# DAC_32CH.net
KiCad netlist of a schematic drawn in Altium Designer
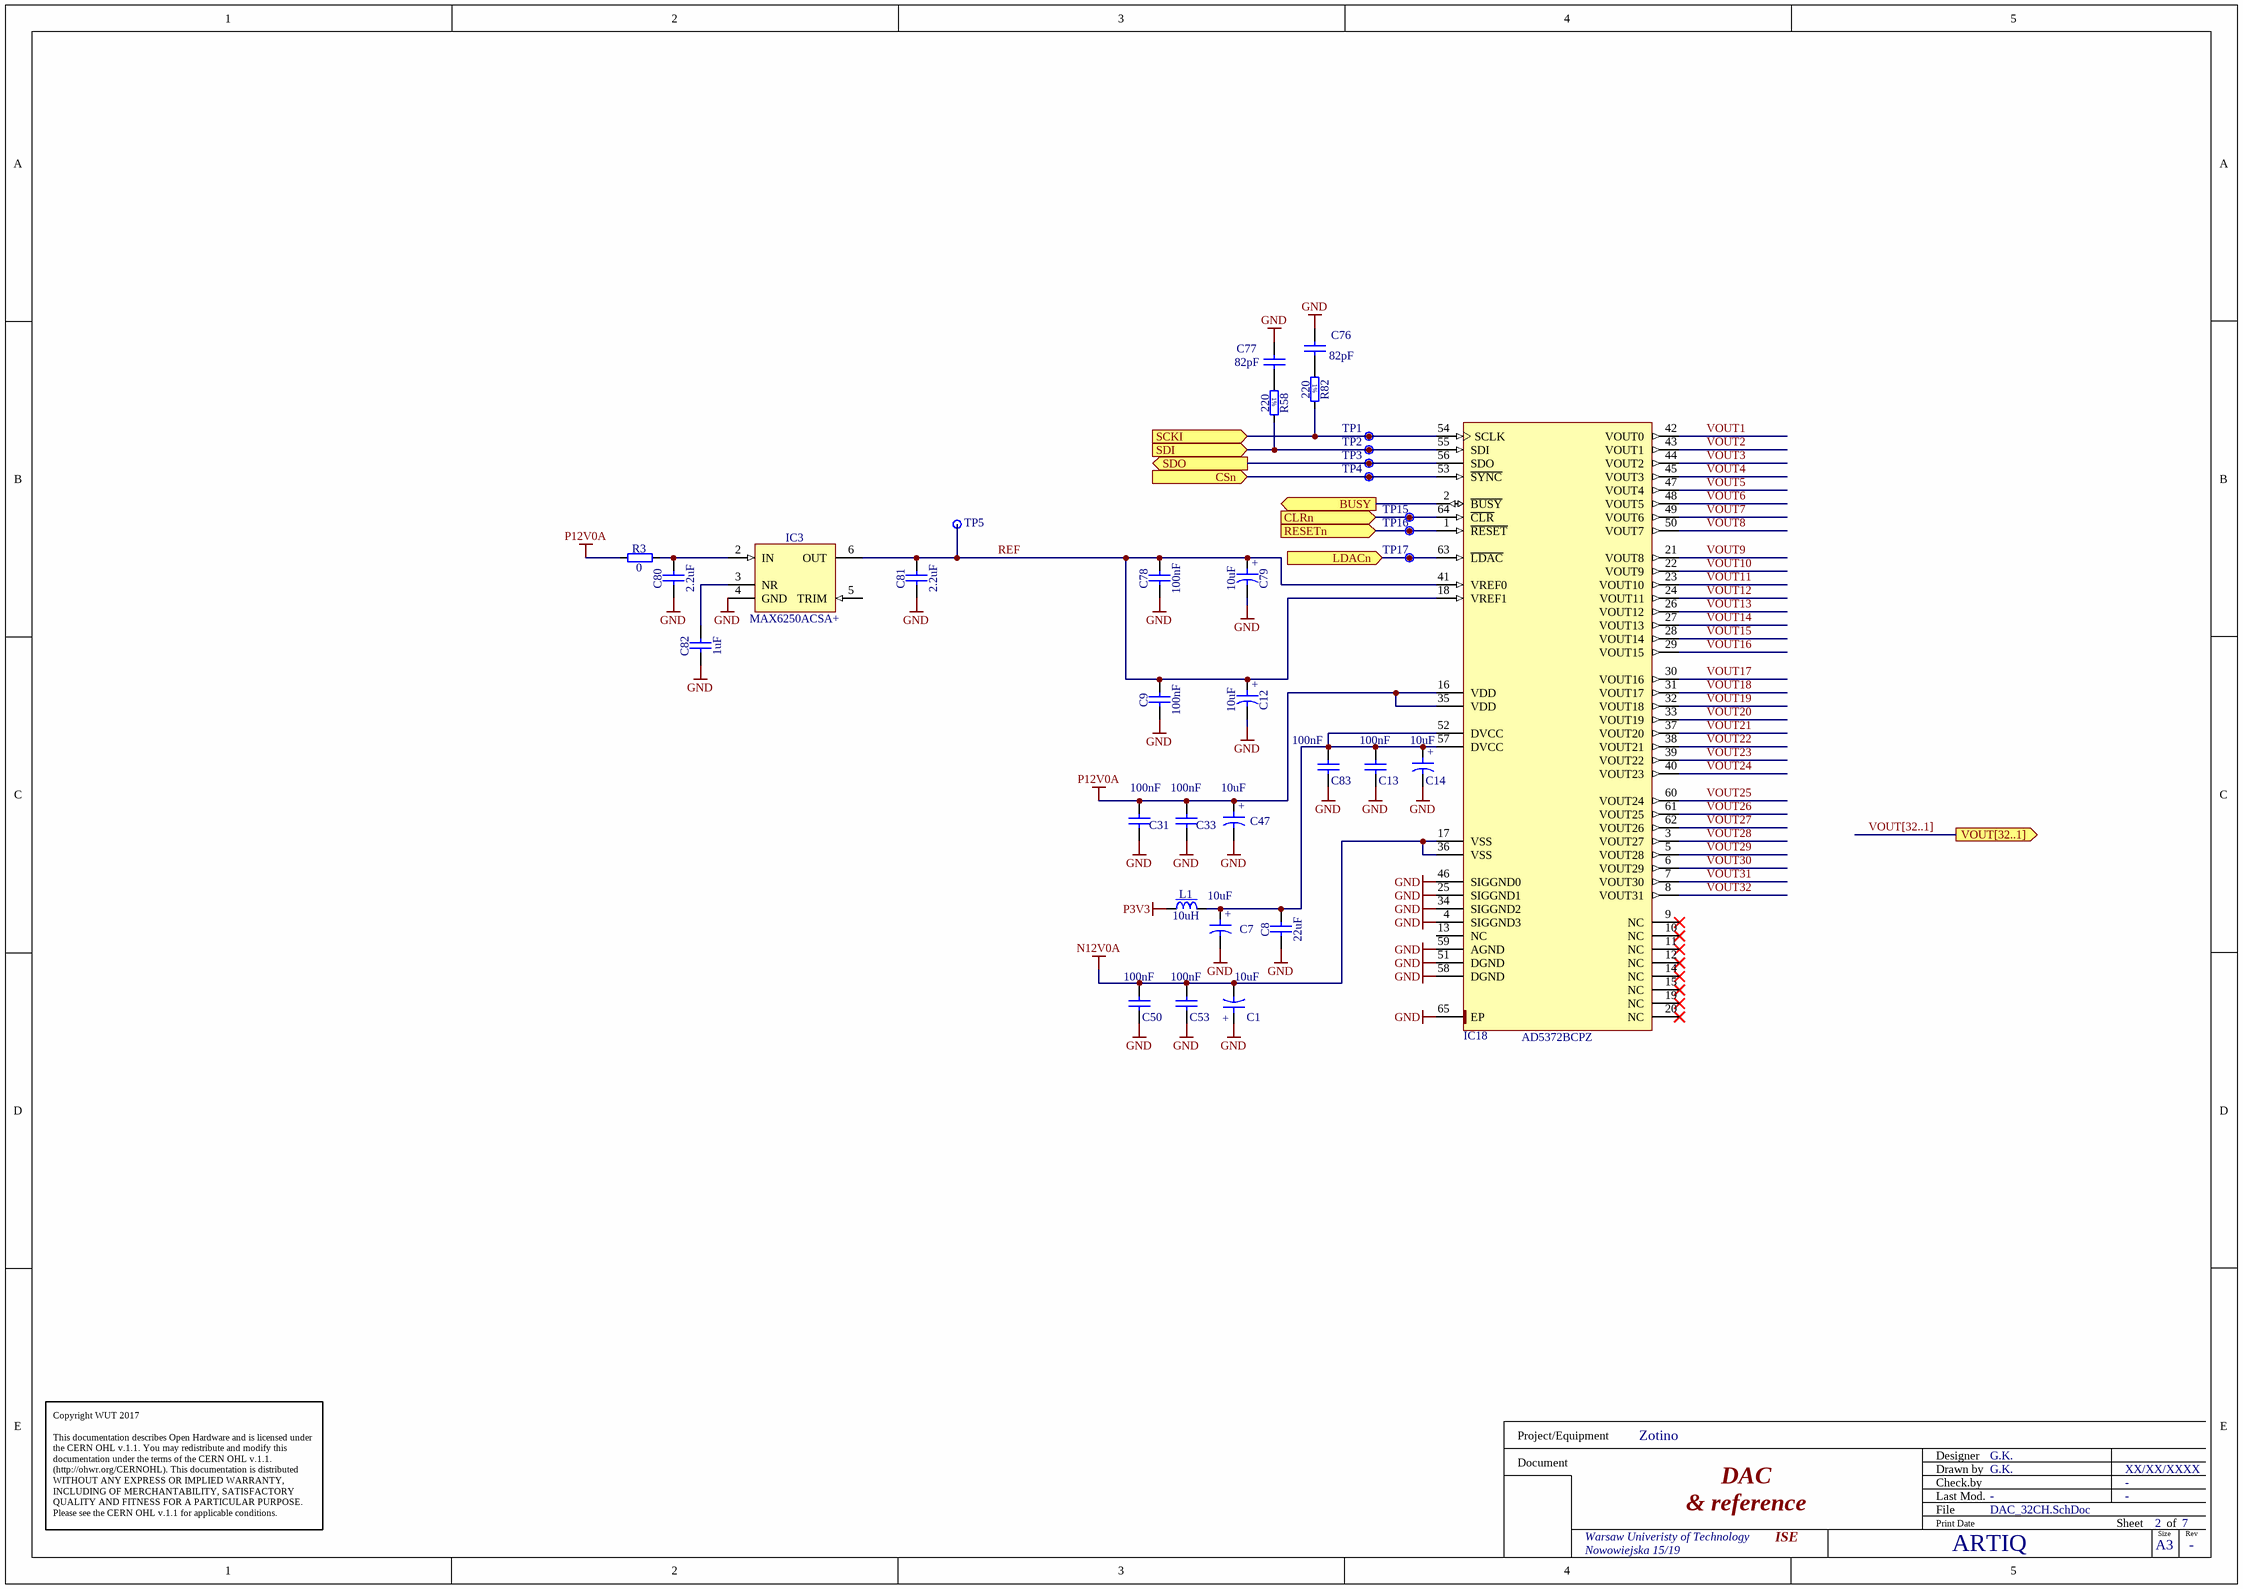
[diagram p0: DAC_32CH.SchDoc]

(export (version "E")
  (design (tool "Eeschema 10.0.6"))
  (components
    (comp (ref "C1")
      (value "10uF")
      (footprint "CAPMP3216X180N")
      (description "Polarised capacitor")
      (fields
        (field (name "PART NUMBER") "CTE3216-18_10UF_16V_20%_AVX_TCJ")
        (field (name "VOLTAGE") "16V")
        (field (name "AUTHOR") "CERN DEM JLC")
      )
      (libsource (lib "Capacitors") (part "Capacitor - polarized"))
    )
    (comp (ref "C7")
      (value "10uF")
      (footprint "CAPMP3216X180N")
      (description "Polarised capacitor")
      (fields
        (field (name "PART NUMBER") "CTE3216-18_10UF_16V_20%_AVX_TCJ")
        (field (name "VOLTAGE") "16V")
        (field (name "AUTHOR") "CERN DEM JLC")
      )
      (libsource (lib "Capacitors") (part "Capacitor - polarized"))
    )
    (comp (ref "C8")
      (value "22uF")
      (footprint "CAPC2012X135N")
      (description "Non-polarised capacitor")
      (fields
        (field (name "PART NUMBER") "CC0805_22UF_16V_10%_X5R")
        (field (name "VOLTAGE") "16V")
        (field (name "AUTHOR") "CERN DEM JLC")
      )
      (libsource (lib "Capacitors") (part "Capacitor - non polarized"))
    )
    (comp (ref "C9")
      (value "100nF")
      (footprint "CAPC1005X55N")
      (description "Non-polarised capacitor")
      (fields
        (field (name "PART NUMBER") "CC0402_100NF_16V_10%_X7R")
        (field (name "VOLTAGE") "16V")
        (field (name "AUTHOR") "CERN DEM JLC")
      )
      (libsource (lib "Capacitors") (part "Capacitor - non polarized"))
    )
    (comp (ref "C12")
      (value "10uF")
      (footprint "CAPMP3216X180N")
      (description "Polarised capacitor")
      (fields
        (field (name "PART NUMBER") "CTE3216-18_10UF_16V_20%_AVX_TCJ")
        (field (name "VOLTAGE") "16V")
        (field (name "AUTHOR") "CERN DEM JLC")
      )
      (libsource (lib "Capacitors") (part "Capacitor - polarized"))
    )
    (comp (ref "C13")
      (value "100nF")
      (footprint "CAPC1005X55N")
      (description "Non-polarised capacitor")
      (fields
        (field (name "PART NUMBER") "CC0402_100NF_16V_10%_X7R")
        (field (name "VOLTAGE") "16V")
        (field (name "AUTHOR") "CERN DEM JLC")
      )
      (libsource (lib "Capacitors") (part "Capacitor - non polarized"))
    )
    (comp (ref "C14")
      (value "10uF")
      (footprint "CAPMP3216X180N")
      (description "Polarised capacitor")
      (fields
        (field (name "PART NUMBER") "CTE3216-18_10UF_16V_20%_AVX_TCJ")
        (field (name "VOLTAGE") "16V")
        (field (name "AUTHOR") "CERN DEM JLC")
      )
      (libsource (lib "Capacitors") (part "Capacitor - polarized"))
    )
    (comp (ref "C31")
      (value "100nF")
      (footprint "CAPC1005X55N")
      (description "Non-polarised capacitor")
      (fields
        (field (name "PART NUMBER") "CC0402_100NF_16V_10%_X7R")
        (field (name "VOLTAGE") "16V")
        (field (name "AUTHOR") "CERN DEM JLC")
      )
      (libsource (lib "Capacitors") (part "Capacitor - non polarized"))
    )
    (comp (ref "C33")
      (value "100nF")
      (footprint "CAPC1005X55N")
      (description "Non-polarised capacitor")
      (fields
        (field (name "PART NUMBER") "CC0402_100NF_16V_10%_X7R")
        (field (name "VOLTAGE") "16V")
        (field (name "AUTHOR") "CERN DEM JLC")
      )
      (libsource (lib "Capacitors") (part "Capacitor - non polarized"))
    )
    (comp (ref "C47")
      (value "10uF")
      (footprint "CAPMP3216X180N")
      (description "Polarised capacitor")
      (fields
        (field (name "PART NUMBER") "CTE3216-18_10UF_16V_20%_AVX_TCJ")
        (field (name "VOLTAGE") "16V")
        (field (name "AUTHOR") "CERN DEM JLC")
      )
      (libsource (lib "Capacitors") (part "Capacitor - polarized"))
    )
    (comp (ref "C50")
      (value "100nF")
      (footprint "CAPC1005X55N")
      (description "Non-polarised capacitor")
      (fields
        (field (name "PART NUMBER") "CC0402_100NF_16V_10%_X7R")
        (field (name "VOLTAGE") "16V")
        (field (name "AUTHOR") "CERN DEM JLC")
      )
      (libsource (lib "Capacitors") (part "Capacitor - non polarized"))
    )
    (comp (ref "C53")
      (value "100nF")
      (footprint "CAPC1005X55N")
      (description "Non-polarised capacitor")
      (fields
        (field (name "PART NUMBER") "CC0402_100NF_16V_10%_X7R")
        (field (name "VOLTAGE") "16V")
        (field (name "AUTHOR") "CERN DEM JLC")
      )
      (libsource (lib "Capacitors") (part "Capacitor - non polarized"))
    )
    (comp (ref "C76")
      (value "82pF")
      (footprint "CAPC1608X87N")
      (description "Non-polarised capacitor")
      (fields
        (field (name "PART NUMBER") "CC0603_82PF_50V_5%_NP0")
        (field (name "VOLTAGE") "50V")
        (field (name "AUTHOR") "CERN DEM JLC")
      )
      (libsource (lib "Capacitors") (part "Capacitor - non polarized"))
    )
    (comp (ref "C77")
      (value "82pF")
      (footprint "CAPC1608X87N")
      (description "Non-polarised capacitor")
      (fields
        (field (name "PART NUMBER") "CC0603_82PF_50V_5%_NP0")
        (field (name "VOLTAGE") "50V")
        (field (name "AUTHOR") "CERN DEM JLC")
      )
      (libsource (lib "Capacitors") (part "Capacitor - non polarized"))
    )
    (comp (ref "C78")
      (value "100nF")
      (footprint "CAPC1005X55N")
      (description "Non-polarised capacitor")
      (fields
        (field (name "PART NUMBER") "CC0402_100NF_16V_10%_X7R")
        (field (name "VOLTAGE") "16V")
        (field (name "AUTHOR") "CERN DEM JLC")
      )
      (libsource (lib "Capacitors") (part "Capacitor - non polarized"))
    )
    (comp (ref "C79")
      (value "10uF")
      (footprint "CAPMP3216X180N")
      (description "Polarised capacitor")
      (fields
        (field (name "PART NUMBER") "CTE3216-18_10UF_16V_20%_AVX_TCJ")
        (field (name "VOLTAGE") "16V")
        (field (name "AUTHOR") "CERN DEM JLC")
      )
      (libsource (lib "Capacitors") (part "Capacitor - polarized"))
    )
    (comp (ref "C80")
      (value "2.2uF")
      (footprint "CAPC1608X87N")
      (description "Non-polarised capacitor")
      (fields
        (field (name "PART NUMBER") "CC0603_2.2UF_16V_10%_X5R")
        (field (name "VOLTAGE") "16V")
        (field (name "AUTHOR") "CERN DEM JLC")
      )
      (libsource (lib "Capacitors") (part "Capacitor - non polarized"))
    )
    (comp (ref "C81")
      (value "2.2uF")
      (footprint "CAPC1608X87N")
      (description "Non-polarised capacitor")
      (fields
        (field (name "PART NUMBER") "CC0603_2.2UF_16V_10%_X5R")
        (field (name "VOLTAGE") "16V")
        (field (name "AUTHOR") "CERN DEM JLC")
      )
      (libsource (lib "Capacitors") (part "Capacitor - non polarized"))
    )
    (comp (ref "C82")
      (value "1uF")
      (footprint "CAPC1608X87N")
      (description "Non-polarised capacitor")
      (fields
        (field (name "PART NUMBER") "CC0603_1UF_25V_10%_X7R")
        (field (name "VOLTAGE") "25V")
        (field (name "AUTHOR") "CERN DEM JLC")
      )
      (libsource (lib "Capacitors") (part "Capacitor - non polarized"))
    )
    (comp (ref "C83")
      (value "100nF")
      (footprint "CAPC1005X55N")
      (description "Non-polarised capacitor")
      (fields
        (field (name "PART NUMBER") "CC0402_100NF_16V_10%_X7R")
        (field (name "VOLTAGE") "16V")
        (field (name "AUTHOR") "CERN DEM JLC")
      )
      (libsource (lib "Capacitors") (part "Capacitor - non polarized"))
    )
    (comp (ref "IC3")
      (value "MAX6250ACSA+")
      (footprint "SOIC127P600X175-8N")
      (description "1ppm/°C, Low-Noise, Precision, +5.000V Voltage Reference")
      (fields (field (name "MANUFACTURER") "MAXIM") (field (name "AUTHOR") "CERN DEM JMW"))
      (libsource (lib "ICs And Semiconductors") (part "MAX6250"))
    )
    (comp (ref "IC18")
      (value "AD5372BCPZ")
      (footprint "QFN50P900X900X100-65N-S725")
      (description "32-Channel, 16-Bit, Serial Input, Voltage Output Digital-to-Analog Converter")
      (fields (field (name "MANUFACTURER") "ANALOG DEVICES") (field (name "AUTHOR") "GK"))
      (libsource (lib "LIBRARY_SCH") (part "DAC_AD5372"))
    )
    (comp (ref "L1")
      (value "10uH")
      (footprint "IND_MURATA-PS_8400")
      (description "Inductor With Core")
      (fields
        (field (name "PART NUMBER") "IND_10UH_10%_MURATA-PS_8400")
        (field (name "POWER") "950mA")
        (field (name "AUTHOR") "CERN DEM JLC")
      )
      (libsource (lib "Inductors & Transformers") (part "Inductor With Magnetic core"))
    )
    (comp (ref "R3")
      (value "0")
      (footprint "RESC1005X40N")
      (description "Resistor")
      (fields
        (field (name "PART NUMBER") "R0402_0R_JUMPER")
        (field (name "MANUFACTURER") "GENERIC")
        (field (name "AUTHOR") "CERN DEM JLC")
      )
      (libsource (lib "Resistors") (part "Resistor"))
    )
    (comp (ref "R58")
      (value "220")
      (footprint "RESC1608X55N")
      (description "Resistor - 1%")
      (fields
        (field (name "PART NUMBER") "R0603_220R_1%_0.1W_100PPM")
        (field (name "POWER") "0.1W")
        (field (name "AUTHOR") "CERN DEM JLC")
      )
      (libsource (lib "Resistors") (part "Resistor - 1%"))
    )
    (comp (ref "R82")
      (value "220")
      (footprint "RESC1608X55N")
      (description "Resistor - 1%")
      (fields
        (field (name "PART NUMBER") "R0603_220R_1%_0.1W_100PPM")
        (field (name "POWER") "0.1W")
        (field (name "AUTHOR") "CERN DEM JLC")
      )
      (libsource (lib "Resistors") (part "Resistor - 1%"))
    )
    (comp (ref "TP1")
      (value "Test Point")
      (footprint "TPS127")
      (fields (field (name "PART NUMBER") "SMD_PAD_1.27X1.27MM") (field (name "AUTHOR") "CERN DEM JLC"))
      (libsource (lib "Eletro-mechanical") (part "Test Point"))
    )
    (comp (ref "TP2")
      (value "Test Point")
      (footprint "TPS127")
      (fields (field (name "PART NUMBER") "SMD_PAD_1.27X1.27MM") (field (name "AUTHOR") "CERN DEM JLC"))
      (libsource (lib "Eletro-mechanical") (part "Test Point"))
    )
    (comp (ref "TP3")
      (value "Test Point")
      (footprint "TPS127")
      (fields (field (name "PART NUMBER") "SMD_PAD_1.27X1.27MM") (field (name "AUTHOR") "CERN DEM JLC"))
      (libsource (lib "Eletro-mechanical") (part "Test Point"))
    )
    (comp (ref "TP4")
      (value "Test Point")
      (footprint "TPS127")
      (fields (field (name "PART NUMBER") "SMD_PAD_1.27X1.27MM") (field (name "AUTHOR") "CERN DEM JLC"))
      (libsource (lib "Eletro-mechanical") (part "Test Point"))
    )
    (comp (ref "TP5")
      (value "Test Point")
      (footprint "TPS127")
      (fields (field (name "PART NUMBER") "SMD_PAD_1.27X1.27MM") (field (name "AUTHOR") "CERN DEM JLC"))
      (libsource (lib "Eletro-mechanical") (part "Test Point"))
    )
    (comp (ref "TP15")
      (value "Test Point")
      (footprint "TPS127")
      (fields (field (name "PART NUMBER") "SMD_PAD_1.27X1.27MM") (field (name "AUTHOR") "CERN DEM JLC"))
      (libsource (lib "Eletro-mechanical") (part "Test Point"))
    )
    (comp (ref "TP16")
      (value "Test Point")
      (footprint "TPS127")
      (fields (field (name "PART NUMBER") "SMD_PAD_1.27X1.27MM") (field (name "AUTHOR") "CERN DEM JLC"))
      (libsource (lib "Eletro-mechanical") (part "Test Point"))
    )
    (comp (ref "TP17")
      (value "Test Point")
      (footprint "TPS127")
      (fields (field (name "PART NUMBER") "SMD_PAD_1.27X1.27MM") (field (name "AUTHOR") "CERN DEM JLC"))
      (libsource (lib "Eletro-mechanical") (part "Test Point"))
    )
  )
  (nets
    (net (code "1") (name "/BUSY") (class "Default")
      (node (ref "IC18") (pin "2") (pinfunction "~{BUSY}_2") (pintype "bidirectional"))
    )
    (net (code "2") (name "/CLRn") (class "Default")
      (node (ref "IC18") (pin "64") (pinfunction "~{CLR}_64") (pintype "input"))
      (node (ref "TP15") (pin "1") (pinfunction "1_1") (pintype "bidirectional"))
    )
    (net (code "3") (name "/CSn") (class "Default")
      (node (ref "IC18") (pin "53") (pinfunction "~{SYNC}_53") (pintype "input"))
      (node (ref "TP4") (pin "1") (pinfunction "1_1") (pintype "bidirectional"))
    )
    (net (code "4") (name "/LDACn") (class "Default")
      (node (ref "IC18") (pin "63") (pinfunction "~{LDAC}_63") (pintype "input"))
      (node (ref "TP17") (pin "1") (pinfunction "1_1") (pintype "bidirectional"))
    )
    (net (code "5") (name "/REF") (class "Default")
      (node (ref "C12") (pin "1") (pinfunction "1_1") (pintype "passive"))
      (node (ref "C78") (pin "2") (pinfunction "2_2") (pintype "passive"))
      (node (ref "C79") (pin "1") (pinfunction "1_1") (pintype "passive"))
      (node (ref "C81") (pin "2") (pinfunction "2_2") (pintype "passive"))
      (node (ref "C9") (pin "2") (pinfunction "2_2") (pintype "passive"))
      (node (ref "IC18") (pin "18") (pinfunction "VREF1_18") (pintype "input"))
      (node (ref "IC18") (pin "41") (pinfunction "VREF0_41") (pintype "input"))
      (node (ref "IC3") (pin "6") (pinfunction "OUT_6") (pintype "power_in"))
      (node (ref "TP5") (pin "1") (pinfunction "1_1") (pintype "bidirectional"))
    )
    (net (code "6") (name "/RESETn") (class "Default")
      (node (ref "IC18") (pin "1") (pinfunction "~{RESET}_1") (pintype "input"))
      (node (ref "TP16") (pin "1") (pinfunction "1_1") (pintype "bidirectional"))
    )
    (net (code "7") (name "/SCKI") (class "Default")
      (node (ref "IC18") (pin "54") (pinfunction "SCLK_54") (pintype "input"))
      (node (ref "R82") (pin "2") (pinfunction "2_2") (pintype "passive"))
      (node (ref "TP1") (pin "1") (pinfunction "1_1") (pintype "bidirectional"))
    )
    (net (code "8") (name "/SDI") (class "Default")
      (node (ref "IC18") (pin "55") (pinfunction "SDI_55") (pintype "input"))
      (node (ref "R58") (pin "2") (pinfunction "2_2") (pintype "passive"))
      (node (ref "TP2") (pin "1") (pinfunction "1_1") (pintype "bidirectional"))
    )
    (net (code "9") (name "/SDO") (class "Default")
      (node (ref "IC18") (pin "56") (pinfunction "SDO_56") (pintype "tri_state"))
      (node (ref "TP3") (pin "1") (pinfunction "1_1") (pintype "bidirectional"))
    )
    (net (code "10") (name "/VOUT1") (class "Default")
      (node (ref "IC18") (pin "42") (pinfunction "VOUT0_42") (pintype "output"))
    )
    (net (code "11") (name "/VOUT2") (class "Default")
      (node (ref "IC18") (pin "43") (pinfunction "VOUT1_43") (pintype "output"))
    )
    (net (code "12") (name "/VOUT3") (class "Default")
      (node (ref "IC18") (pin "44") (pinfunction "VOUT2_44") (pintype "output"))
    )
    (net (code "13") (name "/VOUT4") (class "Default")
      (node (ref "IC18") (pin "45") (pinfunction "VOUT3_45") (pintype "output"))
    )
    (net (code "14") (name "/VOUT5") (class "Default")
      (node (ref "IC18") (pin "47") (pinfunction "VOUT4_47") (pintype "output"))
    )
    (net (code "15") (name "/VOUT6") (class "Default")
      (node (ref "IC18") (pin "48") (pinfunction "VOUT5_48") (pintype "output"))
    )
    (net (code "16") (name "/VOUT7") (class "Default")
      (node (ref "IC18") (pin "49") (pinfunction "VOUT6_49") (pintype "output"))
    )
    (net (code "17") (name "/VOUT8") (class "Default")
      (node (ref "IC18") (pin "50") (pinfunction "VOUT7_50") (pintype "output"))
    )
    (net (code "18") (name "/VOUT9") (class "Default")
      (node (ref "IC18") (pin "21") (pinfunction "VOUT8_21") (pintype "output"))
    )
    (net (code "19") (name "/VOUT10") (class "Default")
      (node (ref "IC18") (pin "22") (pinfunction "VOUT9_22") (pintype "output"))
    )
    (net (code "20") (name "/VOUT11") (class "Default")
      (node (ref "IC18") (pin "23") (pinfunction "VOUT10_23") (pintype "output"))
    )
    (net (code "21") (name "/VOUT12") (class "Default")
      (node (ref "IC18") (pin "24") (pinfunction "VOUT11_24") (pintype "output"))
    )
    (net (code "22") (name "/VOUT13") (class "Default")
      (node (ref "IC18") (pin "26") (pinfunction "VOUT12_26") (pintype "output"))
    )
    (net (code "23") (name "/VOUT14") (class "Default")
      (node (ref "IC18") (pin "27") (pinfunction "VOUT13_27") (pintype "output"))
    )
    (net (code "24") (name "/VOUT15") (class "Default")
      (node (ref "IC18") (pin "28") (pinfunction "VOUT14_28") (pintype "output"))
    )
    (net (code "25") (name "/VOUT16") (class "Default")
      (node (ref "IC18") (pin "29") (pinfunction "VOUT15_29") (pintype "output"))
    )
    (net (code "26") (name "/VOUT17") (class "Default")
      (node (ref "IC18") (pin "30") (pinfunction "VOUT16_30") (pintype "output"))
    )
    (net (code "27") (name "/VOUT18") (class "Default")
      (node (ref "IC18") (pin "31") (pinfunction "VOUT17_31") (pintype "output"))
    )
    (net (code "28") (name "/VOUT19") (class "Default")
      (node (ref "IC18") (pin "32") (pinfunction "VOUT18_32") (pintype "output"))
    )
    (net (code "29") (name "/VOUT20") (class "Default")
      (node (ref "IC18") (pin "33") (pinfunction "VOUT19_33") (pintype "output"))
    )
    (net (code "30") (name "/VOUT21") (class "Default")
      (node (ref "IC18") (pin "37") (pinfunction "VOUT20_37") (pintype "output"))
    )
    (net (code "31") (name "/VOUT22") (class "Default")
      (node (ref "IC18") (pin "38") (pinfunction "VOUT21_38") (pintype "output"))
    )
    (net (code "32") (name "/VOUT23") (class "Default")
      (node (ref "IC18") (pin "39") (pinfunction "VOUT22_39") (pintype "output"))
    )
    (net (code "33") (name "/VOUT24") (class "Default")
      (node (ref "IC18") (pin "40") (pinfunction "VOUT23_40") (pintype "output"))
    )
    (net (code "34") (name "/VOUT25") (class "Default")
      (node (ref "IC18") (pin "60") (pinfunction "VOUT24_60") (pintype "output"))
    )
    (net (code "35") (name "/VOUT26") (class "Default")
      (node (ref "IC18") (pin "61") (pinfunction "VOUT25_61") (pintype "output"))
    )
    (net (code "36") (name "/VOUT27") (class "Default")
      (node (ref "IC18") (pin "62") (pinfunction "VOUT26_62") (pintype "output"))
    )
    (net (code "37") (name "/VOUT28") (class "Default")
      (node (ref "IC18") (pin "3") (pinfunction "VOUT27_3") (pintype "output"))
    )
    (net (code "38") (name "/VOUT29") (class "Default")
      (node (ref "IC18") (pin "5") (pinfunction "VOUT28_5") (pintype "output"))
    )
    (net (code "39") (name "/VOUT30") (class "Default")
      (node (ref "IC18") (pin "6") (pinfunction "VOUT29_6") (pintype "output"))
    )
    (net (code "40") (name "/VOUT31") (class "Default")
      (node (ref "IC18") (pin "7") (pinfunction "VOUT30_7") (pintype "output"))
    )
    (net (code "41") (name "/VOUT32") (class "Default")
      (node (ref "IC18") (pin "8") (pinfunction "VOUT31_8") (pintype "output"))
    )
    (net (code "43") (name "GND") (class "Default")
      (node (ref "C1") (pin "1") (pinfunction "1_1") (pintype "passive"))
      (node (ref "C12") (pin "2") (pinfunction "2_2") (pintype "passive"))
      (node (ref "C13") (pin "1") (pinfunction "1_1") (pintype "passive"))
      (node (ref "C14") (pin "2") (pinfunction "2_2") (pintype "passive"))
      (node (ref "C31") (pin "1") (pinfunction "1_1") (pintype "passive"))
      (node (ref "C33") (pin "1") (pinfunction "1_1") (pintype "passive"))
      (node (ref "C47") (pin "2") (pinfunction "2_2") (pintype "passive"))
      (node (ref "C50") (pin "1") (pinfunction "1_1") (pintype "passive"))
      (node (ref "C53") (pin "1") (pinfunction "1_1") (pintype "passive"))
      (node (ref "C7") (pin "2") (pinfunction "2_2") (pintype "passive"))
      (node (ref "C76") (pin "1") (pinfunction "1_1") (pintype "passive"))
      (node (ref "C77") (pin "1") (pinfunction "1_1") (pintype "passive"))
      (node (ref "C78") (pin "1") (pinfunction "1_1") (pintype "passive"))
      (node (ref "C79") (pin "2") (pinfunction "2_2") (pintype "passive"))
      (node (ref "C8") (pin "1") (pinfunction "1_1") (pintype "passive"))
      (node (ref "C80") (pin "1") (pinfunction "1_1") (pintype "passive"))
      (node (ref "C81") (pin "1") (pinfunction "1_1") (pintype "passive"))
      (node (ref "C82") (pin "1") (pinfunction "1_1") (pintype "passive"))
      (node (ref "C83") (pin "1") (pinfunction "1_1") (pintype "passive"))
      (node (ref "C9") (pin "1") (pinfunction "1_1") (pintype "passive"))
      (node (ref "IC18") (pin "25") (pinfunction "SIGGND1_25") (pintype "power_in"))
      (node (ref "IC18") (pin "34") (pinfunction "SIGGND2_34") (pintype "power_in"))
      (node (ref "IC18") (pin "4") (pinfunction "SIGGND3_4") (pintype "power_in"))
      (node (ref "IC18") (pin "46") (pinfunction "SIGGND0_46") (pintype "power_in"))
      (node (ref "IC18") (pin "51") (pinfunction "DGND_51") (pintype "power_in"))
      (node (ref "IC18") (pin "58") (pinfunction "DGND_58") (pintype "power_in"))
      (node (ref "IC18") (pin "59") (pinfunction "AGND_59") (pintype "power_in"))
      (node (ref "IC18") (pin "65") (pinfunction "EP_65") (pintype "power_in"))
      (node (ref "IC3") (pin "4") (pinfunction "GND_4") (pintype "power_in"))
    )
    (net (code "44") (name "N12V0A") (class "Default")
      (node (ref "C1") (pin "2") (pinfunction "2_2") (pintype "passive"))
      (node (ref "C50") (pin "2") (pinfunction "2_2") (pintype "passive"))
      (node (ref "C53") (pin "2") (pinfunction "2_2") (pintype "passive"))
      (node (ref "IC18") (pin "17") (pinfunction "VSS_17") (pintype "power_in"))
      (node (ref "IC18") (pin "36") (pinfunction "VSS_36") (pintype "power_in"))
    )
    (net (code "45") (name "Net-(C13-Pad2)") (class "Default")
      (node (ref "C13") (pin "2") (pinfunction "2_2") (pintype "passive"))
      (node (ref "C14") (pin "1") (pinfunction "1_1") (pintype "passive"))
      (node (ref "C7") (pin "1") (pinfunction "1_1") (pintype "passive"))
      (node (ref "C8") (pin "2") (pinfunction "2_2") (pintype "passive"))
      (node (ref "C83") (pin "2") (pinfunction "2_2") (pintype "passive"))
      (node (ref "IC18") (pin "52") (pinfunction "DVCC_52") (pintype "power_in"))
      (node (ref "IC18") (pin "57") (pinfunction "DVCC_57") (pintype "power_in"))
      (node (ref "L1") (pin "2") (pinfunction "2_2") (pintype "passive"))
    )
    (net (code "46") (name "Net-(C76-Pad2)") (class "Default")
      (node (ref "C76") (pin "2") (pinfunction "2_2") (pintype "passive"))
      (node (ref "R82") (pin "1") (pinfunction "1_1") (pintype "passive"))
    )
    (net (code "47") (name "Net-(C77-Pad2)") (class "Default")
      (node (ref "C77") (pin "2") (pinfunction "2_2") (pintype "passive"))
      (node (ref "R58") (pin "1") (pinfunction "1_1") (pintype "passive"))
    )
    (net (code "48") (name "Net-(IC3-IN)") (class "Default")
      (node (ref "C80") (pin "2") (pinfunction "2_2") (pintype "passive"))
      (node (ref "IC3") (pin "2") (pinfunction "IN_2") (pintype "input"))
      (node (ref "R3") (pin "2") (pinfunction "2_2") (pintype "passive"))
    )
    (net (code "49") (name "Net-(IC3-NR)") (class "Default")
      (node (ref "C82") (pin "2") (pinfunction "2_2") (pintype "passive"))
      (node (ref "IC3") (pin "3") (pinfunction "NR_3") (pintype "passive"))
    )
    (net (code "50") (name "P3V3") (class "Default")
      (node (ref "L1") (pin "1") (pinfunction "1_1") (pintype "passive"))
    )
    (net (code "51") (name "P12V0A") (class "Default")
      (node (ref "C31") (pin "2") (pinfunction "2_2") (pintype "passive"))
      (node (ref "C33") (pin "2") (pinfunction "2_2") (pintype "passive"))
      (node (ref "C47") (pin "1") (pinfunction "1_1") (pintype "passive"))
      (node (ref "IC18") (pin "16") (pinfunction "VDD_16") (pintype "power_in"))
      (node (ref "IC18") (pin "35") (pinfunction "VDD_35") (pintype "power_in"))
      (node (ref "R3") (pin "1") (pinfunction "1_1") (pintype "passive"))
    )
    (net (code "52") (name "unconnected-(IC3-TRIM-Pad5)") (class "Default")
      (node (ref "IC3") (pin "5") (pinfunction "TRIM_5") (pintype "input"))
    )
    (net (code "53") (name "unconnected-(IC18-NC-Pad9)") (class "Default")
      (node (ref "IC18") (pin "9") (pinfunction "NC_9") (pintype "passive+no_connect"))
    )
    (net (code "54") (name "unconnected-(IC18-NC-Pad10)") (class "Default")
      (node (ref "IC18") (pin "10") (pinfunction "NC_10") (pintype "passive+no_connect"))
    )
    (net (code "55") (name "unconnected-(IC18-NC-Pad11)") (class "Default")
      (node (ref "IC18") (pin "11") (pinfunction "NC_11") (pintype "passive+no_connect"))
    )
    (net (code "56") (name "unconnected-(IC18-NC-Pad12)") (class "Default")
      (node (ref "IC18") (pin "12") (pinfunction "NC_12") (pintype "passive+no_connect"))
    )
    (net (code "57") (name "unconnected-(IC18-NC-Pad13)") (class "Default")
      (node (ref "IC18") (pin "13") (pinfunction "NC_13") (pintype "passive"))
    )
    (net (code "58") (name "unconnected-(IC18-NC-Pad14)") (class "Default")
      (node (ref "IC18") (pin "14") (pinfunction "NC_14") (pintype "passive+no_connect"))
    )
    (net (code "59") (name "unconnected-(IC18-NC-Pad15)") (class "Default")
      (node (ref "IC18") (pin "15") (pinfunction "NC_15") (pintype "passive+no_connect"))
    )
    (net (code "60") (name "unconnected-(IC18-NC-Pad19)") (class "Default")
      (node (ref "IC18") (pin "19") (pinfunction "NC_19") (pintype "passive+no_connect"))
    )
    (net (code "61") (name "unconnected-(IC18-NC-Pad20)") (class "Default")
      (node (ref "IC18") (pin "20") (pinfunction "NC_20") (pintype "passive+no_connect"))
    )
  )
)
